# USB_Serial_CH340G.net
KiCad netlist of a schematic drawn in Altium Designer
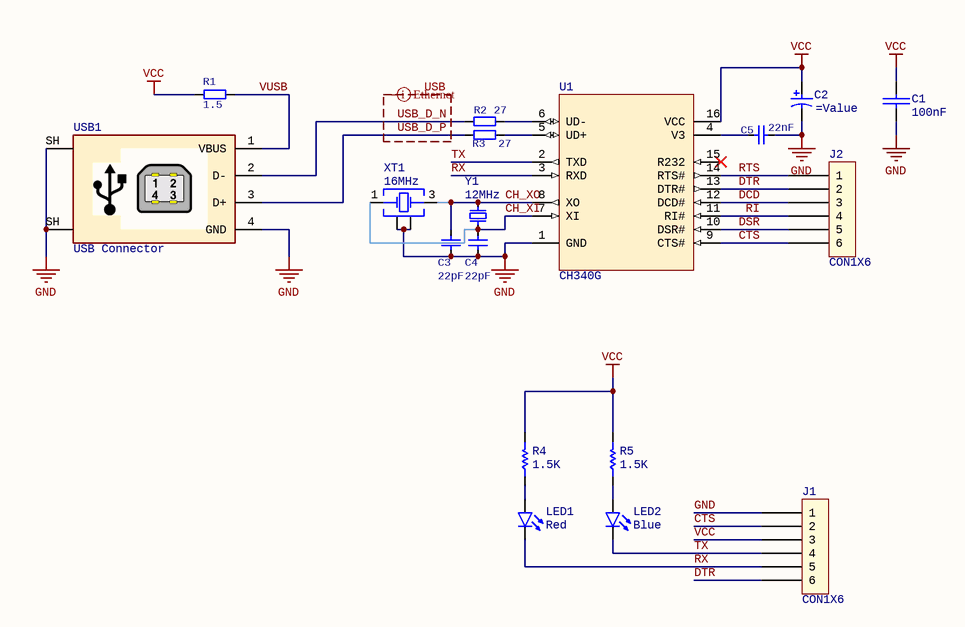
[diagram p0: USB_Serial_CH340G.SchDoc]

(export (version "E")
  (design (tool "Eeschema 10.0.6"))
  (components
    (comp (ref "C1")
      (value "100nF")
      (footprint "CAP 1206 (3216X15L)")
      (description "Bipolar Capacitor")
      (fields (field (name "VOLTAGE") "100V"))
      (libsource (lib "My Library") (part "Cap-Bipolar"))
    )
    (comp (ref "C2")
      (value "~")
      (footprint "CAP SMD A (EIA1206)")
      (description "Tantalum Capacitor, 1uF, 50V, 2-Leads, SMD 1206")
      (fields (field (name "VOLTAGE") "35V"))
      (libsource (lib "Components") (part "CMP-1664-00002-2"))
    )
    (comp (ref "C3")
      (value "22pF")
      (footprint "CAP 1206 (3216X15L)")
      (libsource (lib "Components") (part "C_NP_ASA"))
    )
    (comp (ref "C4")
      (value "22pF")
      (footprint "CAP 1206 (3216X15L)")
      (libsource (lib "Components") (part "C_NP_ASA"))
    )
    (comp (ref "C5") (value "22nF") (footprint "CAP 1206 (3216X15L)") (libsource (lib "*") (part "C_NP_ASA")))
    (comp (ref "J1")
      (value "CON1X6")
      (footprint "Components:HP6")
      (description "CH340 UART Pinout")
      (libsource (lib "HEADER") (part "HEADER-6POS"))
    )
    (comp (ref "J2")
      (value "CON1X6")
      (footprint "Components:HP6")
      (description "CH340 RS-232 Pinout")
      (libsource (lib "HEADER") (part "HEADER-6POS"))
    )
    (comp (ref "LED1")
      (value "RX")
      (footprint "LED 1206 SMD")
      (description "LED 1206 Red")
      (fields (field (name "COLOR") "Red"))
      (libsource (lib "Components") (part "LED"))
    )
    (comp (ref "LED2")
      (value "TX")
      (footprint "LED 1206 SMD")
      (description "LED 1206 Blue")
      (fields (field (name "COLOR") "Blue"))
      (libsource (lib "Components") (part "LED"))
    )
    (comp (ref "R1")
      (value "1.5")
      (footprint "RES 1206 (3216X08L)")
      (libsource (lib "Components") (part "R_ASA"))
    )
    (comp (ref "R2")
      (value "27")
      (footprint "RES 1206 (3216X08L)")
      (libsource (lib "Components") (part "R_ASA"))
    )
    (comp (ref "R3")
      (value "27")
      (footprint "RES 1206 (3216X08L)")
      (libsource (lib "Components") (part "R_ASA"))
    )
    (comp (ref "R4")
      (value "1.5K")
      (footprint "RES 1206 (3216X08L)")
      (description "Resistor")
      (fields (field (name "TOLERANCE") "5%") (field (name "POWER") "1/8 W"))
      (libsource (lib "Components") (part "Resistor"))
    )
    (comp (ref "R5")
      (value "1.5K")
      (footprint "RES 1206 (3216X08L)")
      (description "Resistor")
      (fields (field (name "TOLERANCE") "5%") (field (name "POWER") "1/8 W"))
      (libsource (lib "Components") (part "Resistor"))
    )
    (comp (ref "U1")
      (value "CH340G")
      (footprint "SO-16_M")
      (description "USB to UART Interface SOIC-16 SMD")
      (libsource (lib "Components") (part "CH340G"))
    )
    (comp (ref "USB1")
      (value "USB Connector")
      (footprint "USB2.5-2H4E")
      (description "USB Connector Type-B")
      (libsource (lib "Components") (part "USB-B"))
    )
    (comp (ref "XT1")
      (value "16MHz")
      (footprint "WE-XTAL_CFPX-180")
      (description "XTAL Quartz Crystal, SMT, CFPX-180, 25MHz, +/-10ppm")
      (fields (field (name "MANUFACTURER 1 PARTNO") "830051068"))
      (libsource (lib "WE-XTAL (rev21a)") (part "830051068"))
    )
    (comp (ref "Y1")
      (value "12MHz")
      (footprint "XT_Crystal_SMD")
      (description "Crystal SMD 2-Leads")
      (libsource (lib "Components") (part "XT_ASA"))
    )
  )
  (nets
    (net (code "1") (name "/CH_XI") (class "Default")
      (node (ref "C4") (pin "1") (pinfunction "A_1") (pintype "passive"))
      (node (ref "U1") (pin "7") (pinfunction "XI_7") (pintype "input"))
      (node (ref "XT1") (pin "1") (pinfunction "Crystal_1") (pintype "passive"))
      (node (ref "Y1") (pin "1") (pinfunction "A_1") (pintype "passive"))
    )
    (net (code "2") (name "/CH_XO") (class "Default")
      (node (ref "C3") (pin "2") (pinfunction "B_2") (pintype "passive"))
      (node (ref "U1") (pin "8") (pinfunction "XO_8") (pintype "output"))
      (node (ref "XT1") (pin "3") (pinfunction "Crystal_3") (pintype "passive"))
      (node (ref "Y1") (pin "2") (pinfunction "B_2") (pintype "passive"))
    )
    (net (code "3") (name "/CTS") (class "Default")
      (node (ref "J1") (pin "2") (pinfunction "2_2") (pintype "passive"))
      (node (ref "J2") (pin "6") (pinfunction "6_6") (pintype "passive"))
      (node (ref "U1") (pin "9") (pinfunction "CTS#_9") (pintype "input"))
    )
    (net (code "4") (name "/DCD") (class "Default")
      (node (ref "J2") (pin "3") (pinfunction "3_3") (pintype "passive"))
      (node (ref "U1") (pin "12") (pinfunction "DCD#_12") (pintype "input"))
    )
    (net (code "5") (name "/DSR") (class "Default")
      (node (ref "J2") (pin "5") (pinfunction "5_5") (pintype "passive"))
      (node (ref "U1") (pin "10") (pinfunction "DSR#_10") (pintype "input"))
    )
    (net (code "6") (name "/DTR") (class "Default")
      (node (ref "J1") (pin "6") (pinfunction "6_6") (pintype "passive"))
      (node (ref "J2") (pin "2") (pinfunction "2_2") (pintype "passive"))
      (node (ref "U1") (pin "13") (pinfunction "DTR#_13") (pintype "output"))
    )
    (net (code "7") (name "/RI") (class "Default")
      (node (ref "J2") (pin "4") (pinfunction "4_4") (pintype "passive"))
      (node (ref "U1") (pin "11") (pinfunction "RI#_11") (pintype "input"))
    )
    (net (code "8") (name "/RTS") (class "Default")
      (node (ref "J2") (pin "1") (pinfunction "1_1") (pintype "passive"))
      (node (ref "U1") (pin "14") (pinfunction "RTS#_14") (pintype "output"))
    )
    (net (code "9") (name "/RX") (class "Default")
      (node (ref "J1") (pin "5") (pinfunction "5_5") (pintype "passive"))
      (node (ref "LED1") (pin "2") (pinfunction "K_2") (pintype "passive"))
      (node (ref "U1") (pin "3") (pinfunction "RXD_3") (pintype "input"))
    )
    (net (code "10") (name "/TX") (class "Default")
      (node (ref "J1") (pin "4") (pinfunction "4_4") (pintype "passive"))
      (node (ref "LED2") (pin "2") (pinfunction "K_2") (pintype "passive"))
      (node (ref "U1") (pin "2") (pinfunction "TXD_2") (pintype "output"))
    )
    (net (code "11") (name "/USB_D_N") (class "Default")
      (node (ref "R2") (pin "2") (pinfunction "B_2") (pintype "passive"))
      (node (ref "USB1") (pin "2") (pinfunction "D-_2") (pintype "passive"))
    )
    (net (code "12") (name "/USB_D_P") (class "Default")
      (node (ref "R3") (pin "2") (pinfunction "B_2") (pintype "passive"))
      (node (ref "USB1") (pin "3") (pinfunction "D+_3") (pintype "passive"))
    )
    (net (code "13") (name "/VUSB") (class "Default")
      (node (ref "R1") (pin "2") (pinfunction "B_2") (pintype "passive"))
      (node (ref "USB1") (pin "1") (pinfunction "VBUS_1") (pintype "power_in"))
    )
    (net (code "14") (name "GND") (class "Default")
      (node (ref "C1") (pin "1") (pinfunction "+_1") (pintype "passive"))
      (node (ref "C2") (pin "2") (pinfunction "2_2") (pintype "passive"))
      (node (ref "C3") (pin "1") (pinfunction "A_1") (pintype "passive"))
      (node (ref "C4") (pin "2") (pinfunction "B_2") (pintype "passive"))
      (node (ref "C5") (pin "2") (pinfunction "B_2") (pintype "passive"))
      (node (ref "J1") (pin "1") (pinfunction "1_1") (pintype "passive"))
      (node (ref "U1") (pin "1") (pinfunction "GND_1") (pintype "power_in"))
      (node (ref "USB1") (pin "4") (pinfunction "GND_4") (pintype "power_in"))
      (node (ref "USB1") (pin "SH") (pinfunction "SH_SH") (pintype "passive"))
      (node (ref "XT1") (pin "2") (pinfunction "GND_2") (pintype "passive"))
      (node (ref "XT1") (pin "4") (pinfunction "GND_4") (pintype "passive"))
    )
    (net (code "15") (name "Net-(C5-A)") (class "Default")
      (node (ref "C5") (pin "1") (pinfunction "A_1") (pintype "passive"))
      (node (ref "U1") (pin "4") (pinfunction "V3_4") (pintype "power_in"))
    )
    (net (code "16") (name "Net-(LED1-A)") (class "Default")
      (node (ref "LED1") (pin "1") (pinfunction "A_1") (pintype "passive"))
      (node (ref "R4") (pin "1") (pinfunction "1_1") (pintype "passive"))
    )
    (net (code "17") (name "Net-(LED2-A)") (class "Default")
      (node (ref "LED2") (pin "1") (pinfunction "A_1") (pintype "passive"))
      (node (ref "R5") (pin "1") (pinfunction "1_1") (pintype "passive"))
    )
    (net (code "18") (name "Net-(R2-A)") (class "Default")
      (node (ref "R2") (pin "1") (pinfunction "A_1") (pintype "passive"))
      (node (ref "U1") (pin "6") (pinfunction "UD-_6") (pintype "bidirectional"))
    )
    (net (code "19") (name "Net-(R3-A)") (class "Default")
      (node (ref "R3") (pin "1") (pinfunction "A_1") (pintype "passive"))
      (node (ref "U1") (pin "5") (pinfunction "UD+_5") (pintype "bidirectional"))
    )
    (net (code "20") (name "VCC") (class "Default")
      (node (ref "C1") (pin "2") (pinfunction "-_2") (pintype "passive"))
      (node (ref "C2") (pin "1") (pinfunction "1_1") (pintype "passive"))
      (node (ref "J1") (pin "3") (pinfunction "3_3") (pintype "passive"))
      (node (ref "R1") (pin "1") (pinfunction "A_1") (pintype "passive"))
      (node (ref "R4") (pin "2") (pinfunction "2_2") (pintype "passive"))
      (node (ref "R5") (pin "2") (pinfunction "2_2") (pintype "passive"))
      (node (ref "U1") (pin "16") (pinfunction "VCC_16") (pintype "power_in"))
    )
    (net (code "21") (name "unconnected-(U1-R232-Pad15)") (class "Default")
      (node (ref "U1") (pin "15") (pinfunction "R232_15") (pintype "input+no_connect"))
    )
  )
)
